# weather_station.net
KiCad netlist of a schematic drawn in EAGLE
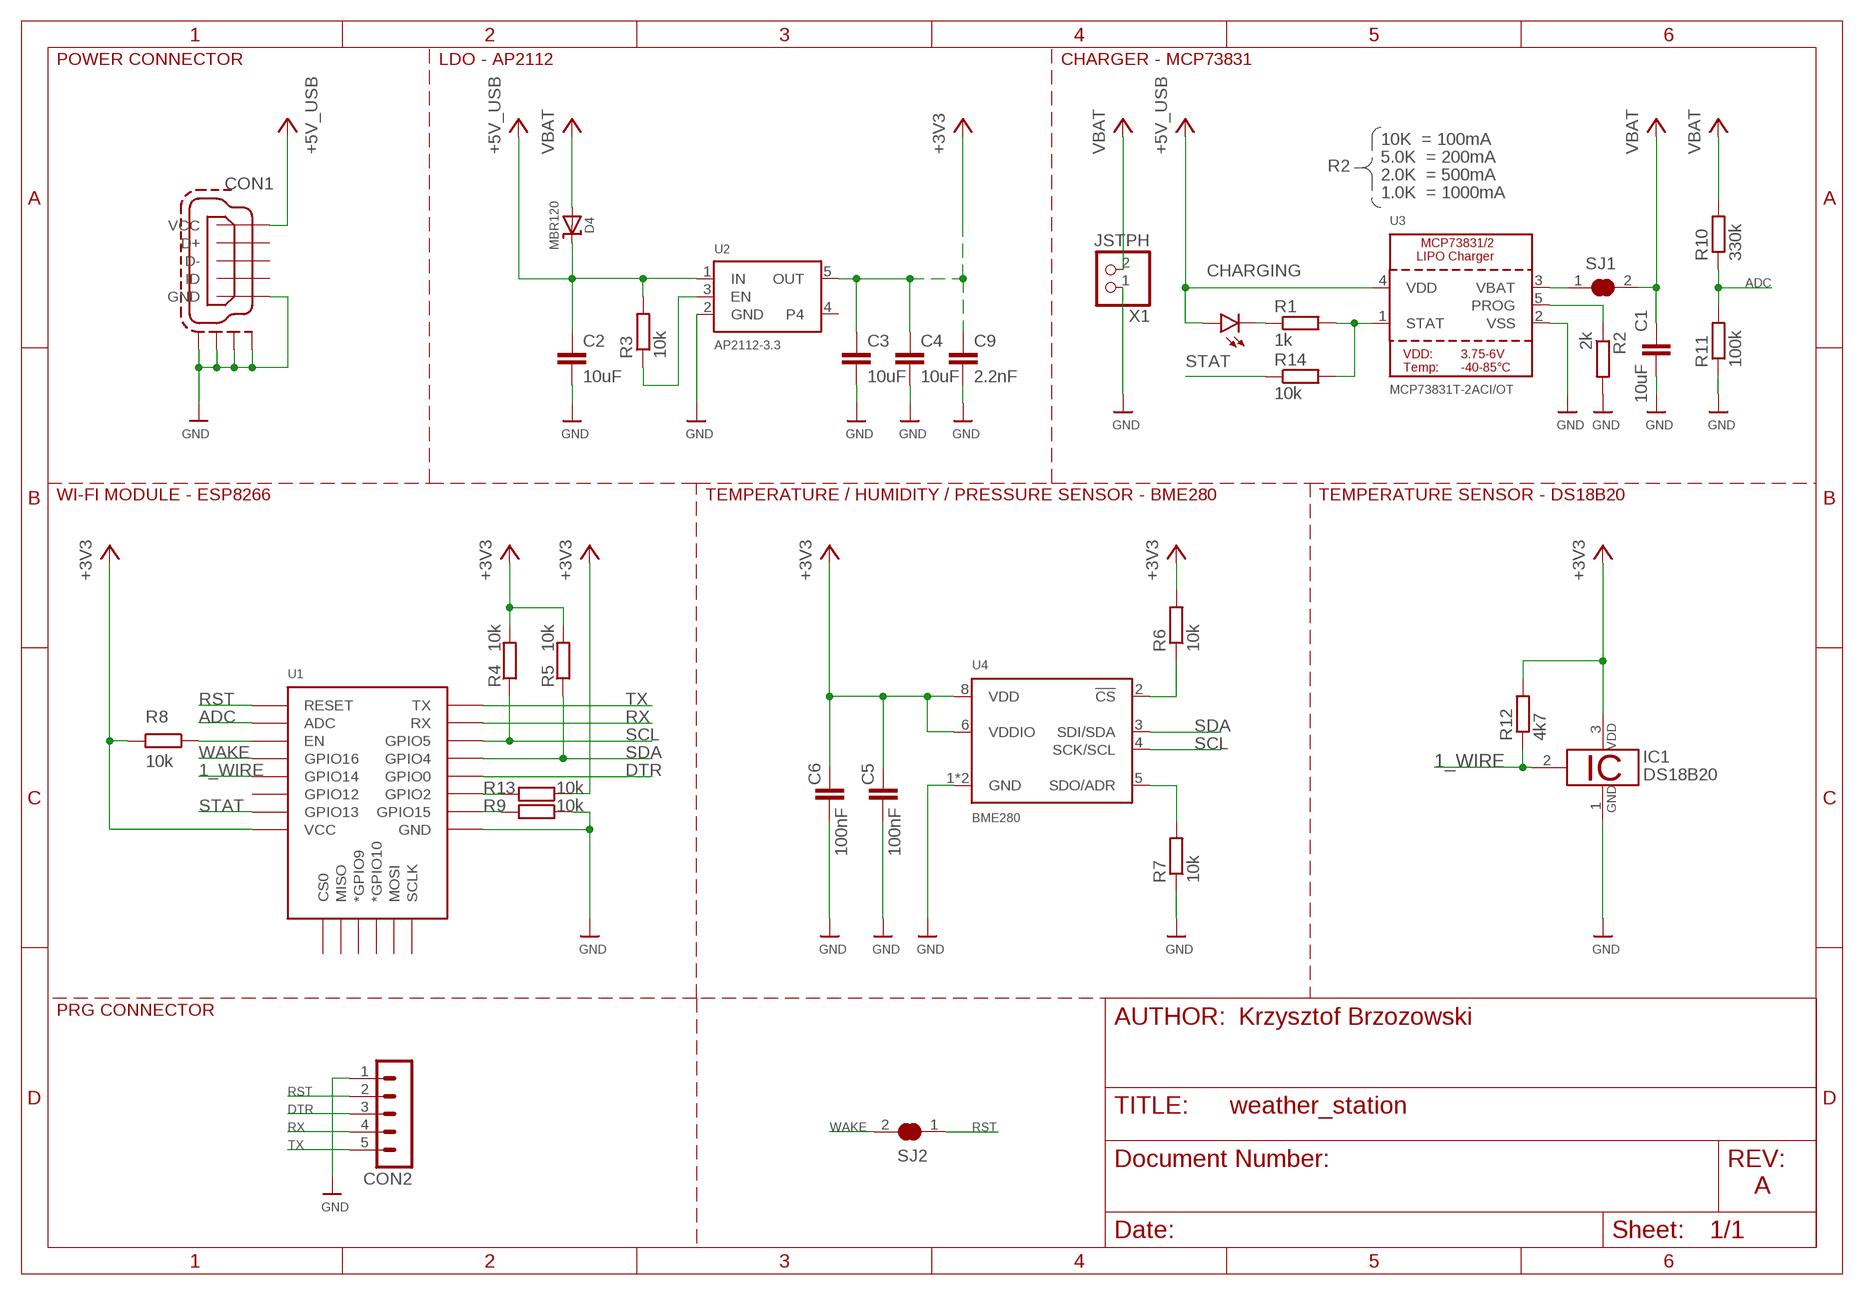
[diagram p0: schematic, sheet 1]

(export (version "E")
  (design (tool "Eeschema 10.0.6"))
  (components
    (comp (ref "C1")
      (value "10uF")
      (footprint "eagle-import:C1210")
      (libsource (lib "eagle-import") (part "C-EUC1210"))
    )
    (comp (ref "C2")
      (value "10uF")
      (footprint "eagle-import:C1210")
      (libsource (lib "eagle-import") (part "C-EUC1210"))
    )
    (comp (ref "C3")
      (value "10uF")
      (footprint "eagle-import:C1210")
      (libsource (lib "eagle-import") (part "C-EUC1210"))
    )
    (comp (ref "C4")
      (value "10uF")
      (footprint "eagle-import:C1210")
      (libsource (lib "eagle-import") (part "C-EUC1210"))
    )
    (comp (ref "C5")
      (value "100nF")
      (footprint "eagle-import:C0402K")
      (libsource (lib "eagle-import") (part "C-EUC0402K"))
    )
    (comp (ref "C6")
      (value "100nF")
      (footprint "eagle-import:C0402K")
      (libsource (lib "eagle-import") (part "C-EUC0402K"))
    )
    (comp (ref "C9")
      (value "2.2nF")
      (footprint "eagle-import:C0402K")
      (libsource (lib "eagle-import") (part "C-EUC0402K"))
    )
    (comp (ref "CHARGING")
      (value "LEDCHIPLED_0603")
      (footprint "eagle-import:CHIPLED_0603")
      (libsource (lib "eagle-import") (part "LEDCHIPLED_0603"))
    )
    (comp (ref "CON1")
      (value "MICROUSB-MOLEX")
      (footprint "eagle-import:MICROUSB-MOLEX")
      (libsource (lib "eagle-import") (part "MICROUSB-MOLEX"))
    )
    (comp (ref "CON2")
      (value "MA05-1")
      (footprint "eagle-import:MA05-1")
      (libsource (lib "eagle-import") (part "MA05-1"))
    )
    (comp (ref "D4")
      (value "MBR120")
      (footprint "eagle-import:SOD-123")
      (libsource (lib "eagle-import") (part "DIODE-SCHOTTKYSOD-123"))
    )
    (comp (ref "IC1")
      (value "DS18B20")
      (footprint "eagle-import:TO92-LNG")
      (libsource (lib "eagle-import") (part "DS18B20T"))
    )
    (comp (ref "R1")
      (value "1k")
      (footprint "eagle-import:R0402")
      (libsource (lib "eagle-import") (part "R-EU_R0402"))
    )
    (comp (ref "R2")
      (value "2k")
      (footprint "eagle-import:R0402")
      (libsource (lib "eagle-import") (part "R-EU_R0402"))
    )
    (comp (ref "R3")
      (value "10k")
      (footprint "eagle-import:R0402")
      (libsource (lib "eagle-import") (part "R-EU_R0402"))
    )
    (comp (ref "R4")
      (value "10k")
      (footprint "eagle-import:R0402")
      (libsource (lib "eagle-import") (part "R-EU_R0402"))
    )
    (comp (ref "R5")
      (value "10k")
      (footprint "eagle-import:R0402")
      (libsource (lib "eagle-import") (part "R-EU_R0402"))
    )
    (comp (ref "R6")
      (value "10k")
      (footprint "eagle-import:R0402")
      (libsource (lib "eagle-import") (part "R-EU_R0402"))
    )
    (comp (ref "R7")
      (value "10k")
      (footprint "eagle-import:R0402")
      (libsource (lib "eagle-import") (part "R-EU_R0402"))
    )
    (comp (ref "R8")
      (value "10k")
      (footprint "eagle-import:R0402")
      (libsource (lib "eagle-import") (part "R-EU_R0402"))
    )
    (comp (ref "R9")
      (value "10k")
      (footprint "eagle-import:R0402")
      (libsource (lib "eagle-import") (part "R-EU_R0402"))
    )
    (comp (ref "R10")
      (value "330k")
      (footprint "eagle-import:R0402")
      (libsource (lib "eagle-import") (part "R-EU_R0402"))
    )
    (comp (ref "R11")
      (value "100k")
      (footprint "eagle-import:R0402")
      (libsource (lib "eagle-import") (part "R-EU_R0402"))
    )
    (comp (ref "R12")
      (value "4k7")
      (footprint "eagle-import:R0402")
      (libsource (lib "eagle-import") (part "R-EU_R0402"))
    )
    (comp (ref "R13")
      (value "10k")
      (footprint "eagle-import:R0402")
      (libsource (lib "eagle-import") (part "R-EU_R0402"))
    )
    (comp (ref "R14")
      (value "10k")
      (footprint "eagle-import:R0402")
      (libsource (lib "eagle-import") (part "R-EU_R0402"))
    )
    (comp (ref "SJ1")
      (value "SOLDERJUMPER_CLOSED")
      (footprint "eagle-import:SOLDERJUMPER_CLOSEDWIRE")
      (libsource (lib "eagle-import") (part "SOLDERJUMPER_CLOSED"))
    )
    (comp (ref "SJ2")
      (value "SOLDERJUMPER_CLOSED")
      (footprint "eagle-import:SOLDERJUMPER_CLOSEDWIRE")
      (libsource (lib "eagle-import") (part "SOLDERJUMPER_CLOSED"))
    )
    (comp (ref "U1")
      (value "ESP12ESMD")
      (footprint "eagle-import:ESP12E-SMD")
      (libsource (lib "eagle-import") (part "ESP12ESMD"))
    )
    (comp (ref "U2")
      (value "AP2112-3.3")
      (footprint "eagle-import:SOT23-5")
      (libsource (lib "eagle-import") (part "VREG_SOT23-5"))
    )
    (comp (ref "U3")
      (value "MCP73831T-2ACI/OT")
      (footprint "eagle-import:SOT23-5")
      (libsource (lib "eagle-import") (part "MCP73831/2"))
    )
    (comp (ref "U4")
      (value "BME280")
      (footprint "eagle-import:LGA-8-2.5X2.5")
      (libsource (lib "eagle-import") (part "BME280"))
    )
    (comp (ref "X1")
      (value "JSTPH")
      (footprint "eagle-import:JSTPH2")
      (libsource (lib "eagle-import") (part "CON_JST_PH_2PIN"))
    )
  )
  (nets
    (net (code "1") (name "+3V3") (class "Default")
      (node (ref "C3") (pin "1") (pinfunction "1_1") (pintype "passive"))
      (node (ref "C4") (pin "1") (pinfunction "1_1") (pintype "passive"))
      (node (ref "C5") (pin "1") (pinfunction "1_1") (pintype "passive"))
      (node (ref "C6") (pin "1") (pinfunction "1_1") (pintype "passive"))
      (node (ref "C9") (pin "1") (pinfunction "1_1") (pintype "passive"))
      (node (ref "IC1") (pin "3") (pinfunction "VDD_3") (pintype "power_in"))
      (node (ref "R12") (pin "2") (pinfunction "2_2") (pintype "passive"))
      (node (ref "R13") (pin "1") (pinfunction "1_1") (pintype "passive"))
      (node (ref "R4") (pin "2") (pinfunction "2_2") (pintype "passive"))
      (node (ref "R5") (pin "2") (pinfunction "2_2") (pintype "passive"))
      (node (ref "R6") (pin "2") (pinfunction "2_2") (pintype "passive"))
      (node (ref "R8") (pin "2") (pinfunction "2_2") (pintype "passive"))
      (node (ref "U1") (pin "VCC") (pinfunction "VCC_VCC") (pintype "bidirectional"))
      (node (ref "U2") (pin "5") (pinfunction "OUT_5") (pintype "power_in"))
      (node (ref "U4") (pin "6") (pinfunction "VDDIO_6") (pintype "bidirectional"))
      (node (ref "U4") (pin "8") (pinfunction "VDD_8") (pintype "bidirectional"))
    )
    (net (code "2") (name "+5V_USB") (class "Default")
      (node (ref "C2") (pin "1") (pinfunction "1_1") (pintype "passive"))
      (node (ref "CHARGING") (pin "A") (pinfunction "A_A") (pintype "passive"))
      (node (ref "CON1") (pin "VCC") (pinfunction "VCC_VCC") (pintype "passive"))
      (node (ref "D4") (pin "C") (pinfunction "C_C") (pintype "passive"))
      (node (ref "R3") (pin "2") (pinfunction "2_2") (pintype "passive"))
      (node (ref "U2") (pin "1") (pinfunction "IN_1") (pintype "power_in"))
      (node (ref "U3") (pin "4") (pinfunction "VDD_4") (pintype "power_in"))
    )
    (net (code "3") (name "/1_WIRE") (class "Default")
      (node (ref "IC1") (pin "2") (pinfunction "1W_2") (pintype "power_in"))
      (node (ref "R12") (pin "1") (pinfunction "1_1") (pintype "passive"))
      (node (ref "U1") (pin "GPIO14") (pinfunction "GPIO14_GPIO14") (pintype "bidirectional"))
    )
    (net (code "4") (name "/ADC") (class "Default")
      (node (ref "R10") (pin "1") (pinfunction "1_1") (pintype "passive"))
      (node (ref "R11") (pin "2") (pinfunction "2_2") (pintype "passive"))
      (node (ref "U1") (pin "ADC") (pinfunction "ADC_ADC") (pintype "bidirectional"))
    )
    (net (code "5") (name "/DTR") (class "Default")
      (node (ref "CON2") (pin "3") (pinfunction "3_3") (pintype "passive"))
      (node (ref "U1") (pin "GPIO0") (pinfunction "GPIO0_GPIO0") (pintype "bidirectional"))
    )
    (net (code "6") (name "/RST") (class "Default")
      (node (ref "CON2") (pin "2") (pinfunction "2_2") (pintype "passive"))
      (node (ref "SJ2") (pin "1") (pinfunction "1_1") (pintype "passive"))
      (node (ref "U1") (pin "RESET") (pinfunction "RESET_RESET") (pintype "bidirectional"))
    )
    (net (code "7") (name "/RX") (class "Default")
      (node (ref "CON2") (pin "4") (pinfunction "4_4") (pintype "passive"))
      (node (ref "U1") (pin "RXD0") (pinfunction "RX_RXD0") (pintype "bidirectional"))
    )
    (net (code "8") (name "/SCL") (class "Default")
      (node (ref "R4") (pin "1") (pinfunction "1_1") (pintype "passive"))
      (node (ref "U1") (pin "GPIO5") (pinfunction "GPIO5_GPIO5") (pintype "bidirectional"))
      (node (ref "U4") (pin "4") (pinfunction "SCK/SCL_4") (pintype "bidirectional"))
    )
    (net (code "9") (name "/SDA") (class "Default")
      (node (ref "R5") (pin "1") (pinfunction "1_1") (pintype "passive"))
      (node (ref "U1") (pin "GPIO4") (pinfunction "GPIO4_GPIO4") (pintype "bidirectional"))
      (node (ref "U4") (pin "3") (pinfunction "SDI/SDA_3") (pintype "bidirectional"))
    )
    (net (code "10") (name "/STAT") (class "Default")
      (node (ref "R14") (pin "1") (pinfunction "1_1") (pintype "passive"))
      (node (ref "U1") (pin "GPIO13") (pinfunction "GPIO13_GPIO13") (pintype "bidirectional"))
    )
    (net (code "11") (name "/TX") (class "Default")
      (node (ref "CON2") (pin "5") (pinfunction "5_5") (pintype "passive"))
      (node (ref "U1") (pin "TXD0") (pinfunction "TX_TXD0") (pintype "bidirectional"))
    )
    (net (code "12") (name "/WAKE") (class "Default")
      (node (ref "SJ2") (pin "2") (pinfunction "2_2") (pintype "passive"))
      (node (ref "U1") (pin "GPIO16") (pinfunction "GPIO16_GPIO16") (pintype "bidirectional"))
    )
    (net (code "13") (name "GND") (class "Default")
      (node (ref "C1") (pin "2") (pinfunction "2_2") (pintype "passive"))
      (node (ref "C2") (pin "2") (pinfunction "2_2") (pintype "passive"))
      (node (ref "C3") (pin "2") (pinfunction "2_2") (pintype "passive"))
      (node (ref "C4") (pin "2") (pinfunction "2_2") (pintype "passive"))
      (node (ref "C5") (pin "2") (pinfunction "2_2") (pintype "passive"))
      (node (ref "C6") (pin "2") (pinfunction "2_2") (pintype "passive"))
      (node (ref "C9") (pin "2") (pinfunction "2_2") (pintype "passive"))
      (node (ref "CON1") (pin "GND") (pinfunction "GND_GND") (pintype "passive"))
      (node (ref "CON1") (pin "GND_H_00") (pinfunction "SH1_GND_H_00") (pintype "passive"))
      (node (ref "CON1") (pin "GND_H_01") (pinfunction "SH2_GND_H_01") (pintype "passive"))
      (node (ref "CON1") (pin "GND_H_02") (pinfunction "SH3_GND_H_02") (pintype "passive"))
      (node (ref "CON1") (pin "GND_H_03") (pinfunction "SH3_GND_H_03") (pintype "passive"))
      (node (ref "CON1") (pin "GND_H_04") (pinfunction "SH3_GND_H_04") (pintype "passive"))
      (node (ref "CON1") (pin "GND_H_05") (pinfunction "SH3_GND_H_05") (pintype "passive"))
      (node (ref "CON1") (pin "GND_H_06") (pinfunction "SH3_GND_H_06") (pintype "passive"))
      (node (ref "CON1") (pin "GND_H_07") (pinfunction "SH3_GND_H_07") (pintype "passive"))
      (node (ref "CON1") (pin "GND_H_08") (pinfunction "SH3_GND_H_08") (pintype "passive"))
      (node (ref "CON1") (pin "GND_H_09") (pinfunction "SH3_GND_H_09") (pintype "passive"))
      (node (ref "CON1") (pin "GND_H_10") (pinfunction "SH3_GND_H_10") (pintype "passive"))
      (node (ref "CON1") (pin "GND_H_11") (pinfunction "SH3_GND_H_11") (pintype "passive"))
      (node (ref "CON1") (pin "GND_H_12") (pinfunction "SH3_GND_H_12") (pintype "passive"))
      (node (ref "CON1") (pin "GND_H_13") (pinfunction "SH4_GND_H_13") (pintype "passive"))
      (node (ref "CON1") (pin "GND_H_14") (pinfunction "SH4_GND_H_14") (pintype "passive"))
      (node (ref "CON1") (pin "GND_H_15") (pinfunction "SH4_GND_H_15") (pintype "passive"))
      (node (ref "CON1") (pin "GND_H_16") (pinfunction "SH4_GND_H_16") (pintype "passive"))
      (node (ref "CON1") (pin "GND_H_17") (pinfunction "SH4_GND_H_17") (pintype "passive"))
      (node (ref "CON1") (pin "GND_H_18") (pinfunction "SH4_GND_H_18") (pintype "passive"))
      (node (ref "CON1") (pin "GND_H_19") (pinfunction "SH4_GND_H_19") (pintype "passive"))
      (node (ref "CON1") (pin "GND_H_20") (pinfunction "SH4_GND_H_20") (pintype "passive"))
      (node (ref "CON1") (pin "GND_H_21") (pinfunction "SH4_GND_H_21") (pintype "passive"))
      (node (ref "CON1") (pin "GND_H_22") (pinfunction "SH4_GND_H_22") (pintype "passive"))
      (node (ref "CON1") (pin "GND_H_23") (pinfunction "SH4_GND_H_23") (pintype "passive"))
      (node (ref "CON1") (pin "GND_P_0") (pinfunction "SH3_GND_P_0") (pintype "passive"))
      (node (ref "CON1") (pin "GND_P_1") (pinfunction "SH3_GND_P_1") (pintype "passive"))
      (node (ref "CON1") (pin "GND_P_2") (pinfunction "SH4_GND_P_2") (pintype "passive"))
      (node (ref "CON1") (pin "GND_P_3") (pinfunction "SH4_GND_P_3") (pintype "passive"))
      (node (ref "CON2") (pin "1") (pinfunction "1_1") (pintype "passive"))
      (node (ref "IC1") (pin "1") (pinfunction "GND_1") (pintype "power_in"))
      (node (ref "R11") (pin "1") (pinfunction "1_1") (pintype "passive"))
      (node (ref "R2") (pin "2") (pinfunction "2_2") (pintype "passive"))
      (node (ref "R7") (pin "1") (pinfunction "1_1") (pintype "passive"))
      (node (ref "R9") (pin "1") (pinfunction "1_1") (pintype "passive"))
      (node (ref "U1") (pin "GND") (pinfunction "GND_GND") (pintype "bidirectional"))
      (node (ref "U2") (pin "2") (pinfunction "GND_2") (pintype "power_in"))
      (node (ref "U3") (pin "2") (pinfunction "VSS_2") (pintype "power_in"))
      (node (ref "U4") (pin "1") (pinfunction "GND_1") (pintype "bidirectional"))
      (node (ref "U4") (pin "7") (pinfunction "GND_7") (pintype "bidirectional"))
      (node (ref "X1") (pin "1") (pinfunction "1_1") (pintype "passive"))
    )
    (net (code "14") (name "Net-(CHARGING-PadC)") (class "Default")
      (node (ref "CHARGING") (pin "C") (pinfunction "C_C") (pintype "passive"))
      (node (ref "R1") (pin "1") (pinfunction "1_1") (pintype "passive"))
    )
    (net (code "15") (name "Net-(R9-Pad2)") (class "Default")
      (node (ref "R9") (pin "2") (pinfunction "2_2") (pintype "passive"))
      (node (ref "U1") (pin "GPIO15") (pinfunction "GPIO15_GPIO15") (pintype "bidirectional"))
    )
    (net (code "16") (name "Net-(R13-Pad2)") (class "Default")
      (node (ref "R13") (pin "2") (pinfunction "2_2") (pintype "passive"))
      (node (ref "U1") (pin "GPIO2") (pinfunction "GPIO2_GPIO2") (pintype "bidirectional"))
    )
    (net (code "17") (name "Net-(U1-EN)") (class "Default")
      (node (ref "R8") (pin "1") (pinfunction "1_1") (pintype "passive"))
      (node (ref "U1") (pin "CH_PD") (pinfunction "EN_CH_PD") (pintype "bidirectional"))
    )
    (net (code "18") (name "Net-(U2-EN)") (class "Default")
      (node (ref "R3") (pin "1") (pinfunction "1_1") (pintype "passive"))
      (node (ref "U2") (pin "3") (pinfunction "EN_3") (pintype "input"))
    )
    (net (code "19") (name "Net-(U3-PROG)") (class "Default")
      (node (ref "R2") (pin "1") (pinfunction "1_1") (pintype "passive"))
      (node (ref "U3") (pin "5") (pinfunction "PROG_5") (pintype "input"))
    )
    (net (code "20") (name "Net-(U3-STAT)") (class "Default")
      (node (ref "R1") (pin "2") (pinfunction "2_2") (pintype "passive"))
      (node (ref "R14") (pin "2") (pinfunction "2_2") (pintype "passive"))
      (node (ref "U3") (pin "1") (pinfunction "STAT_1") (pintype "output"))
    )
    (net (code "21") (name "Net-(U3-VBAT)") (class "Default")
      (node (ref "SJ1") (pin "1") (pinfunction "1_1") (pintype "passive"))
      (node (ref "U3") (pin "3") (pinfunction "VBAT_3") (pintype "power_in"))
    )
    (net (code "22") (name "Net-(U4-SDO{slash}ADR)") (class "Default")
      (node (ref "R7") (pin "2") (pinfunction "2_2") (pintype "passive"))
      (node (ref "U4") (pin "5") (pinfunction "SDO/ADR_5") (pintype "bidirectional"))
    )
    (net (code "23") (name "Net-(U4-~{CS})") (class "Default")
      (node (ref "R6") (pin "1") (pinfunction "1_1") (pintype "passive"))
      (node (ref "U4") (pin "2") (pinfunction "~{CS}_2") (pintype "bidirectional"))
    )
    (net (code "24") (name "VBAT") (class "Default")
      (node (ref "C1") (pin "1") (pinfunction "1_1") (pintype "passive"))
      (node (ref "D4") (pin "A") (pinfunction "A_A") (pintype "passive"))
      (node (ref "R10") (pin "2") (pinfunction "2_2") (pintype "passive"))
      (node (ref "SJ1") (pin "2") (pinfunction "2_2") (pintype "passive"))
      (node (ref "X1") (pin "2") (pinfunction "2_2") (pintype "passive"))
    )
    (net (code "25") (name "unconnected-(CON1-PadD+)") (class "Default")
      (node (ref "CON1") (pin "D+") (pinfunction "D+_D+") (pintype "passive"))
    )
    (net (code "26") (name "unconnected-(CON1-PadD-)") (class "Default")
      (node (ref "CON1") (pin "D-") (pinfunction "D-_D-") (pintype "passive"))
    )
    (net (code "27") (name "unconnected-(CON1-PadID)") (class "Default")
      (node (ref "CON1") (pin "ID") (pinfunction "ID_ID") (pintype "passive"))
    )
    (net (code "28") (name "unconnected-(U1-*GPIO9-PadGPIO9)") (class "Default")
      (node (ref "U1") (pin "GPIO9") (pinfunction "*GPIO9_GPIO9") (pintype "bidirectional"))
    )
    (net (code "29") (name "unconnected-(U1-*GPIO10-PadGPIO10)") (class "Default")
      (node (ref "U1") (pin "GPIO10") (pinfunction "*GPIO10_GPIO10") (pintype "bidirectional"))
    )
    (net (code "30") (name "unconnected-(U1-PadCS0)") (class "Default")
      (node (ref "U1") (pin "CS0") (pinfunction "CS0_CS0") (pintype "bidirectional"))
    )
    (net (code "31") (name "unconnected-(U1-PadGPIO12)") (class "Default")
      (node (ref "U1") (pin "GPIO12") (pinfunction "GPIO12_GPIO12") (pintype "bidirectional"))
    )
    (net (code "32") (name "unconnected-(U1-PadMISO)") (class "Default")
      (node (ref "U1") (pin "MISO") (pinfunction "MISO_MISO") (pintype "bidirectional"))
    )
    (net (code "33") (name "unconnected-(U1-PadMOSI)") (class "Default")
      (node (ref "U1") (pin "MOSI") (pinfunction "MOSI_MOSI") (pintype "bidirectional"))
    )
    (net (code "34") (name "unconnected-(U1-PadSCLK)") (class "Default")
      (node (ref "U1") (pin "SCLK") (pinfunction "SCLK_SCLK") (pintype "bidirectional"))
    )
    (net (code "35") (name "unconnected-(U2-P4-Pad4)") (class "Default")
      (node (ref "U2") (pin "4") (pinfunction "P4_4") (pintype "bidirectional"))
    )
  )
)
